# cyberstick3_new.net
KiCad netlist of a schematic drawn in EAGLE
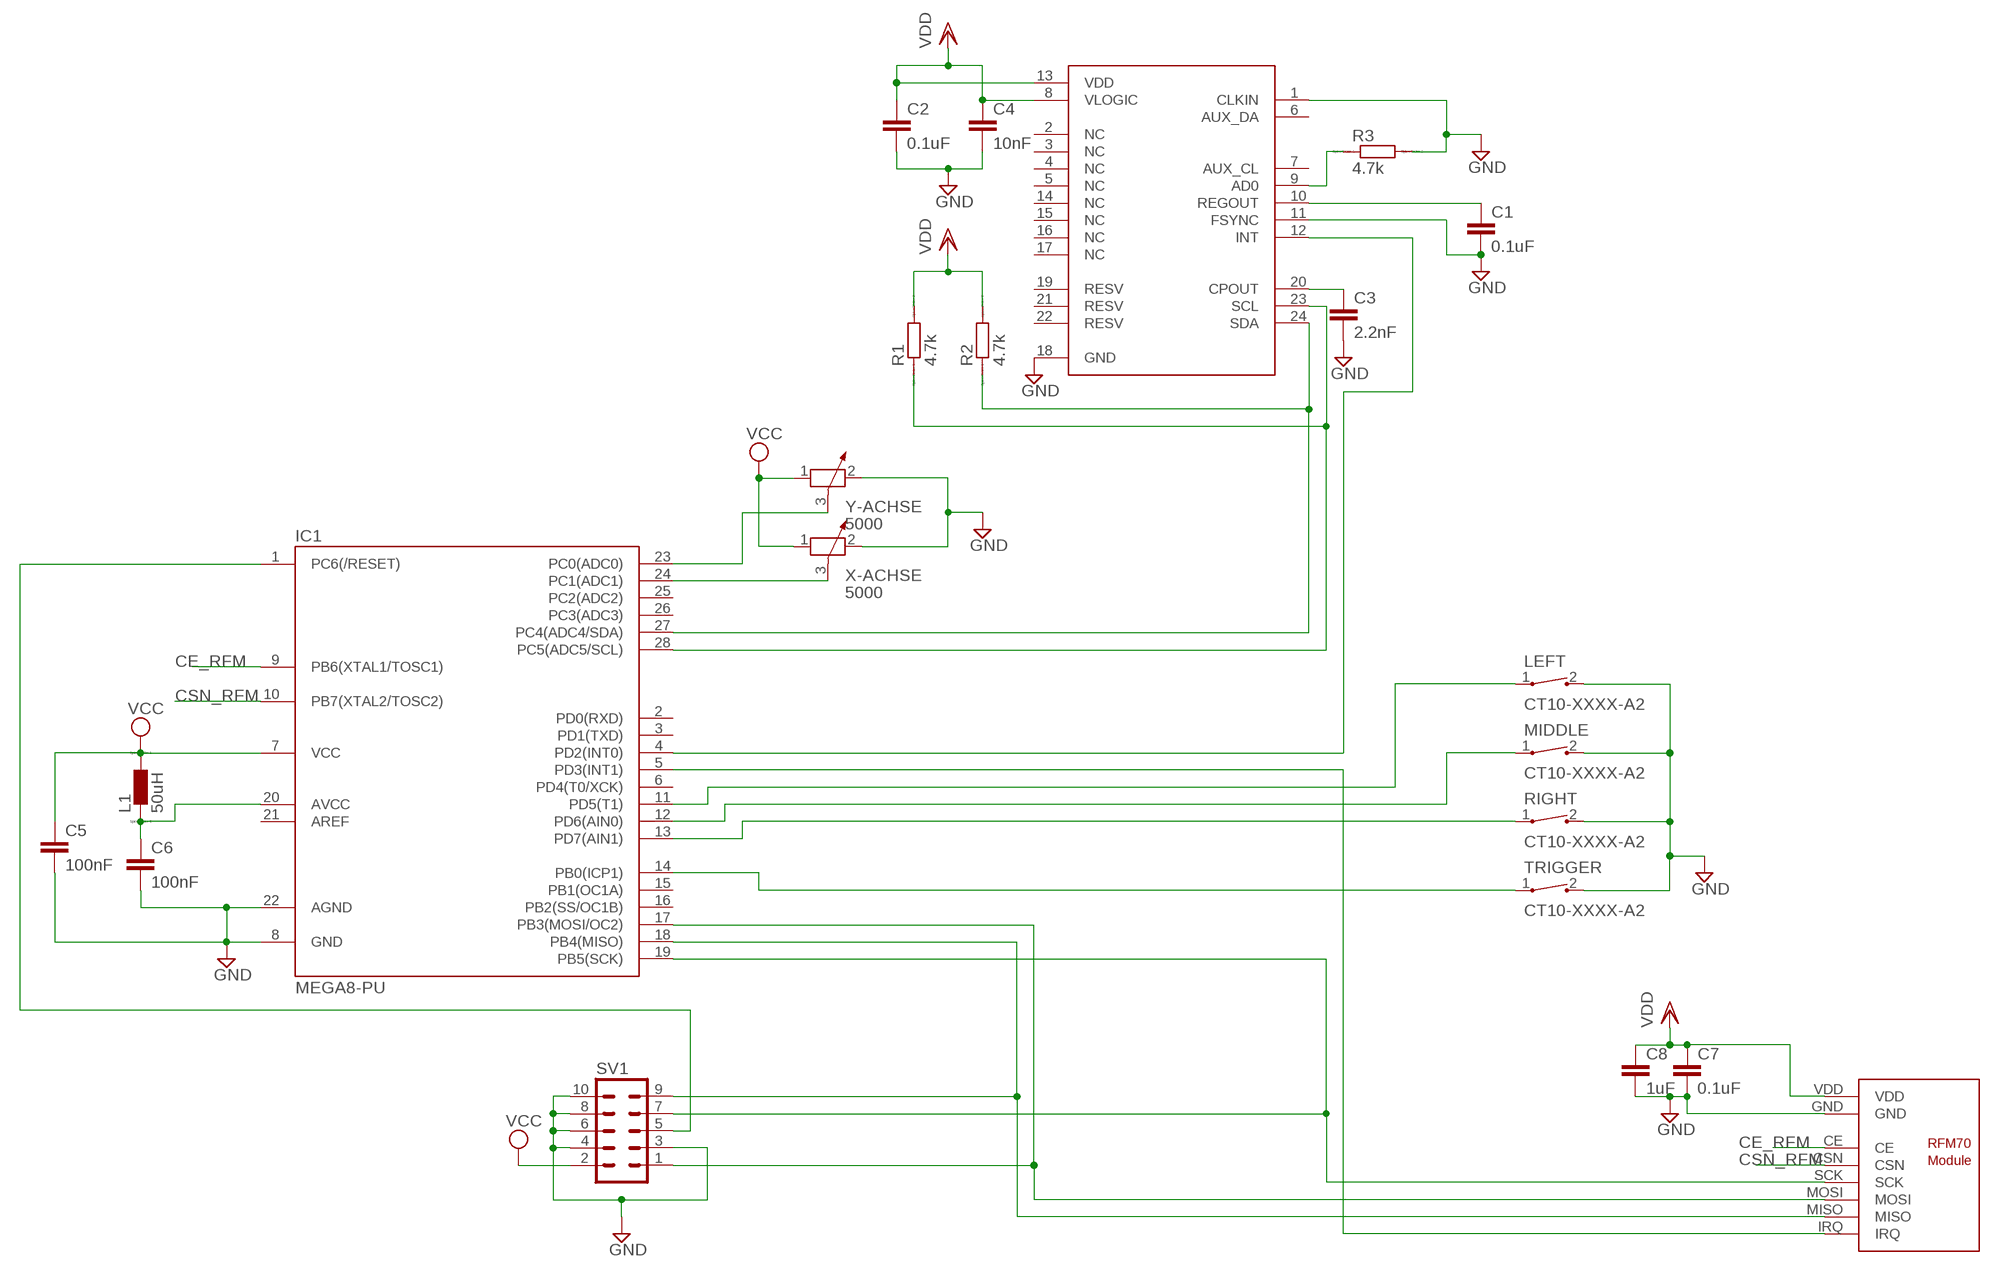
[diagram p0: schematic, sheet 1]

(export (version "E")
  (design (tool "Eeschema 10.0.6"))
  (components
    (comp (ref "C1")
      (value "0.1uF")
      (footprint "eagle-import:C2.5-3")
      (libsource (lib "eagle-import") (part "C2,5-3"))
    )
    (comp (ref "C2")
      (value "0.1uF")
      (footprint "eagle-import:C2.5-3")
      (libsource (lib "eagle-import") (part "C2,5-3"))
    )
    (comp (ref "C3")
      (value "2.2nF")
      (footprint "eagle-import:C2.5-3")
      (libsource (lib "eagle-import") (part "C2,5-3"))
    )
    (comp (ref "C4")
      (value "10nF")
      (footprint "eagle-import:C2.5-3")
      (libsource (lib "eagle-import") (part "C2,5-3"))
    )
    (comp (ref "C5")
      (value "100nF")
      (footprint "eagle-import:C2.5-3")
      (libsource (lib "eagle-import") (part "C2,5-3"))
    )
    (comp (ref "C6")
      (value "100nF")
      (footprint "eagle-import:C2.5-3")
      (libsource (lib "eagle-import") (part "C2,5-3"))
    )
    (comp (ref "C7")
      (value "0.1uF")
      (footprint "eagle-import:C2.5-3")
      (libsource (lib "eagle-import") (part "C2,5-3"))
    )
    (comp (ref "C8")
      (value "1uF")
      (footprint "eagle-import:C2.5-3")
      (libsource (lib "eagle-import") (part "C2,5-3"))
    )
    (comp (ref "IC1")
      (value "MEGA8-PU")
      (footprint "eagle-import:DIL28-3")
      (libsource (lib "eagle-import") (part "MEGA8-PU"))
    )
    (comp (ref "L1")
      (value "50uH")
      (footprint "eagle-import:0204_7")
      (libsource (lib "eagle-import") (part "L0204/7"))
    )
    (comp (ref "LEFT")
      (value "CT10-XXXX-A2")
      (footprint "eagle-import:CT10-XXXX-A2")
      (libsource (lib "eagle-import") (part "CT10-XXXX-A2"))
    )
    (comp (ref "MIDDLE")
      (value "CT10-XXXX-A2")
      (footprint "eagle-import:CT10-XXXX-A2")
      (libsource (lib "eagle-import") (part "CT10-XXXX-A2"))
    )
    (comp (ref "R1")
      (value "4.7k")
      (footprint "eagle-import:0204_7")
      (libsource (lib "eagle-import") (part "R0204/7"))
    )
    (comp (ref "R2")
      (value "4.7k")
      (footprint "eagle-import:0204_7")
      (libsource (lib "eagle-import") (part "R0204/7"))
    )
    (comp (ref "R3")
      (value "4.7k")
      (footprint "eagle-import:0204_7")
      (libsource (lib "eagle-import") (part "R0204/7"))
    )
    (comp (ref "RIGHT")
      (value "CT10-XXXX-A2")
      (footprint "eagle-import:CT10-XXXX-A2")
      (libsource (lib "eagle-import") (part "CT10-XXXX-A2"))
    )
    (comp (ref "SV1")
      (value "MA05-2")
      (footprint "eagle-import:MA05-2")
      (libsource (lib "eagle-import") (part "MA05-2"))
    )
    (comp (ref "TRIGGER")
      (value "CT10-XXXX-A2")
      (footprint "eagle-import:CT10-XXXX-A2")
      (libsource (lib "eagle-import") (part "CT10-XXXX-A2"))
    )
    (comp (ref "U$2")
      (value "RFM70")
      (footprint "eagle-import:RFM70")
      (libsource (lib "eagle-import") (part "RFM70"))
    )
    (comp (ref "U1")
      (value "MPU6050")
      (footprint "eagle-import:MPU6050")
      (libsource (lib "eagle-import") (part "MPU6050"))
    )
    (comp (ref "X-ACHSE")
      (value "5000")
      (footprint "eagle-import:PT-10")
      (libsource (lib "eagle-import") (part "POTENTIOMETER_PT-10"))
    )
    (comp (ref "Y-ACHSE")
      (value "5000")
      (footprint "eagle-import:PT-10")
      (libsource (lib "eagle-import") (part "POTENTIOMETER_PT-10"))
    )
  )
  (nets
    (net (code "1") (name "/CE_RFM") (class "Default")
      (node (ref "IC1") (pin "9") (pinfunction "PB6(XTAL1/TOSC1)_9") (pintype "bidirectional"))
      (node (ref "U$2") (pin "CE") (pinfunction "CE_CE") (pintype "bidirectional"))
    )
    (net (code "2") (name "/CSN_RFM") (class "Default")
      (node (ref "IC1") (pin "10") (pinfunction "PB7(XTAL2/TOSC2)_10") (pintype "bidirectional"))
      (node (ref "U$2") (pin "CSN") (pinfunction "CSN_CSN") (pintype "bidirectional"))
    )
    (net (code "3") (name "GND") (class "Default")
      (node (ref "C1") (pin "2") (pinfunction "2_2") (pintype "passive"))
      (node (ref "C2") (pin "2") (pinfunction "2_2") (pintype "passive"))
      (node (ref "C3") (pin "2") (pinfunction "2_2") (pintype "passive"))
      (node (ref "C4") (pin "2") (pinfunction "2_2") (pintype "passive"))
      (node (ref "C5") (pin "2") (pinfunction "2_2") (pintype "passive"))
      (node (ref "C6") (pin "2") (pinfunction "2_2") (pintype "passive"))
      (node (ref "C7") (pin "2") (pinfunction "2_2") (pintype "passive"))
      (node (ref "C8") (pin "2") (pinfunction "2_2") (pintype "passive"))
      (node (ref "IC1") (pin "22") (pinfunction "AGND_22") (pintype "power_in"))
      (node (ref "IC1") (pin "8") (pinfunction "GND_8") (pintype "power_in"))
      (node (ref "LEFT") (pin "2") (pinfunction "2_2") (pintype "passive"))
      (node (ref "MIDDLE") (pin "2") (pinfunction "2_2") (pintype "passive"))
      (node (ref "R3") (pin "2") (pinfunction "2_2") (pintype "passive"))
      (node (ref "RIGHT") (pin "2") (pinfunction "2_2") (pintype "passive"))
      (node (ref "SV1") (pin "10") (pinfunction "10_10") (pintype "passive"))
      (node (ref "SV1") (pin "3") (pinfunction "3_3") (pintype "passive"))
      (node (ref "SV1") (pin "4") (pinfunction "4_4") (pintype "passive"))
      (node (ref "SV1") (pin "6") (pinfunction "6_6") (pintype "passive"))
      (node (ref "SV1") (pin "8") (pinfunction "8_8") (pintype "passive"))
      (node (ref "TRIGGER") (pin "2") (pinfunction "2_2") (pintype "passive"))
      (node (ref "U$2") (pin "GND") (pinfunction "GND_GND") (pintype "power_in"))
      (node (ref "U1") (pin "1") (pinfunction "CLKIN_1") (pintype "input"))
      (node (ref "U1") (pin "11") (pinfunction "FSYNC_11") (pintype "input"))
      (node (ref "U1") (pin "18") (pinfunction "GND_18") (pintype "power_in"))
      (node (ref "X-ACHSE") (pin "2") (pinfunction "2_2") (pintype "passive"))
      (node (ref "Y-ACHSE") (pin "2") (pinfunction "2_2") (pintype "passive"))
    )
    (net (code "4") (name "Net-(IC1-AVCC)") (class "Default")
      (node (ref "C6") (pin "1") (pinfunction "1_1") (pintype "passive"))
      (node (ref "IC1") (pin "20") (pinfunction "AVCC_20") (pintype "passive"))
      (node (ref "L1") (pin "2") (pinfunction "2_2") (pintype "passive"))
    )
    (net (code "5") (name "Net-(IC1-PB0(ICP1))") (class "Default")
      (node (ref "IC1") (pin "14") (pinfunction "PB0(ICP1)_14") (pintype "bidirectional"))
      (node (ref "TRIGGER") (pin "1") (pinfunction "1_1") (pintype "passive"))
    )
    (net (code "6") (name "Net-(IC1-PB3(MOSI{slash}OC2))") (class "Default")
      (node (ref "IC1") (pin "17") (pinfunction "PB3(MOSI/OC2)_17") (pintype "bidirectional"))
      (node (ref "SV1") (pin "1") (pinfunction "1_1") (pintype "passive"))
      (node (ref "U$2") (pin "MOSI") (pinfunction "MOSI_MOSI") (pintype "bidirectional"))
    )
    (net (code "7") (name "Net-(IC1-PB4(MISO))") (class "Default")
      (node (ref "IC1") (pin "18") (pinfunction "PB4(MISO)_18") (pintype "bidirectional"))
      (node (ref "SV1") (pin "9") (pinfunction "9_9") (pintype "passive"))
      (node (ref "U$2") (pin "MISO") (pinfunction "MISO_MISO") (pintype "bidirectional"))
    )
    (net (code "8") (name "Net-(IC1-PB5(SCK))") (class "Default")
      (node (ref "IC1") (pin "19") (pinfunction "PB5(SCK)_19") (pintype "bidirectional"))
      (node (ref "SV1") (pin "7") (pinfunction "7_7") (pintype "passive"))
      (node (ref "U$2") (pin "SCK") (pinfunction "SCK_SCK") (pintype "bidirectional"))
    )
    (net (code "9") (name "Net-(IC1-PC0(ADC0))") (class "Default")
      (node (ref "IC1") (pin "23") (pinfunction "PC0(ADC0)_23") (pintype "bidirectional"))
      (node (ref "Y-ACHSE") (pin "3") (pinfunction "3_3") (pintype "passive"))
    )
    (net (code "10") (name "Net-(IC1-PC1(ADC1))") (class "Default")
      (node (ref "IC1") (pin "24") (pinfunction "PC1(ADC1)_24") (pintype "bidirectional"))
      (node (ref "X-ACHSE") (pin "3") (pinfunction "3_3") (pintype "passive"))
    )
    (net (code "11") (name "Net-(IC1-PC4(ADC4{slash}SDA))") (class "Default")
      (node (ref "IC1") (pin "27") (pinfunction "PC4(ADC4/SDA)_27") (pintype "bidirectional"))
      (node (ref "R2") (pin "1") (pinfunction "1_1") (pintype "passive"))
      (node (ref "U1") (pin "24") (pinfunction "SDA_24") (pintype "bidirectional"))
    )
    (net (code "12") (name "Net-(IC1-PC5(ADC5{slash}SCL))") (class "Default")
      (node (ref "IC1") (pin "28") (pinfunction "PC5(ADC5/SCL)_28") (pintype "bidirectional"))
      (node (ref "R1") (pin "1") (pinfunction "1_1") (pintype "passive"))
      (node (ref "U1") (pin "23") (pinfunction "SCL_23") (pintype "input"))
    )
    (net (code "13") (name "Net-(IC1-PC6({slash}RESET))") (class "Default")
      (node (ref "IC1") (pin "1") (pinfunction "PC6(/RESET)_1") (pintype "bidirectional"))
      (node (ref "SV1") (pin "5") (pinfunction "5_5") (pintype "passive"))
    )
    (net (code "14") (name "Net-(IC1-PD2(INT0))") (class "Default")
      (node (ref "IC1") (pin "4") (pinfunction "PD2(INT0)_4") (pintype "bidirectional"))
      (node (ref "U1") (pin "12") (pinfunction "INT_12") (pintype "output"))
    )
    (net (code "15") (name "Net-(IC1-PD3(INT1))") (class "Default")
      (node (ref "IC1") (pin "5") (pinfunction "PD3(INT1)_5") (pintype "bidirectional"))
      (node (ref "U$2") (pin "IRQ") (pinfunction "IRQ_IRQ") (pintype "bidirectional"))
    )
    (net (code "16") (name "Net-(IC1-PD5(T1))") (class "Default")
      (node (ref "IC1") (pin "11") (pinfunction "PD5(T1)_11") (pintype "bidirectional"))
      (node (ref "LEFT") (pin "1") (pinfunction "1_1") (pintype "passive"))
    )
    (net (code "17") (name "Net-(IC1-PD6(AIN0))") (class "Default")
      (node (ref "IC1") (pin "12") (pinfunction "PD6(AIN0)_12") (pintype "bidirectional"))
      (node (ref "MIDDLE") (pin "1") (pinfunction "1_1") (pintype "passive"))
    )
    (net (code "18") (name "Net-(IC1-PD7(AIN1))") (class "Default")
      (node (ref "IC1") (pin "13") (pinfunction "PD7(AIN1)_13") (pintype "bidirectional"))
      (node (ref "RIGHT") (pin "1") (pinfunction "1_1") (pintype "passive"))
    )
    (net (code "19") (name "Net-(U1-AD0)") (class "Default")
      (node (ref "R3") (pin "1") (pinfunction "1_1") (pintype "passive"))
      (node (ref "U1") (pin "9") (pinfunction "AD0_9") (pintype "input"))
    )
    (net (code "20") (name "Net-(U1-CPOUT)") (class "Default")
      (node (ref "C3") (pin "1") (pinfunction "1_1") (pintype "passive"))
      (node (ref "U1") (pin "20") (pinfunction "CPOUT_20") (pintype "passive"))
    )
    (net (code "21") (name "Net-(U1-REGOUT)") (class "Default")
      (node (ref "C1") (pin "1") (pinfunction "1_1") (pintype "passive"))
      (node (ref "U1") (pin "10") (pinfunction "REGOUT_10") (pintype "passive"))
    )
    (net (code "22") (name "VCC") (class "Default")
      (node (ref "C5") (pin "1") (pinfunction "1_1") (pintype "passive"))
      (node (ref "IC1") (pin "7") (pinfunction "VCC_7") (pintype "power_in"))
      (node (ref "L1") (pin "1") (pinfunction "1_1") (pintype "passive"))
      (node (ref "SV1") (pin "2") (pinfunction "2_2") (pintype "passive"))
      (node (ref "X-ACHSE") (pin "1") (pinfunction "1_1") (pintype "passive"))
      (node (ref "Y-ACHSE") (pin "1") (pinfunction "1_1") (pintype "passive"))
    )
    (net (code "23") (name "VDD") (class "Default")
      (node (ref "C2") (pin "1") (pinfunction "1_1") (pintype "passive"))
      (node (ref "C4") (pin "1") (pinfunction "1_1") (pintype "passive"))
      (node (ref "C7") (pin "1") (pinfunction "1_1") (pintype "passive"))
      (node (ref "C8") (pin "1") (pinfunction "1_1") (pintype "passive"))
      (node (ref "R1") (pin "2") (pinfunction "2_2") (pintype "passive"))
      (node (ref "R2") (pin "2") (pinfunction "2_2") (pintype "passive"))
      (node (ref "U$2") (pin "VDD") (pinfunction "VDD_VDD") (pintype "power_in"))
      (node (ref "U1") (pin "13") (pinfunction "VDD_13") (pintype "power_in"))
      (node (ref "U1") (pin "8") (pinfunction "VLOGIC_8") (pintype "power_in"))
    )
    (net (code "24") (name "unconnected-(IC1-AREF-Pad21)") (class "Default")
      (node (ref "IC1") (pin "21") (pinfunction "AREF_21") (pintype "passive"))
    )
    (net (code "25") (name "unconnected-(IC1-PB1(OC1A)-Pad15)") (class "Default")
      (node (ref "IC1") (pin "15") (pinfunction "PB1(OC1A)_15") (pintype "bidirectional"))
    )
    (net (code "26") (name "unconnected-(IC1-PB2(SS{slash}OC1B)-Pad16)") (class "Default")
      (node (ref "IC1") (pin "16") (pinfunction "PB2(SS/OC1B)_16") (pintype "bidirectional"))
    )
    (net (code "27") (name "unconnected-(IC1-PC2(ADC2)-Pad25)") (class "Default")
      (node (ref "IC1") (pin "25") (pinfunction "PC2(ADC2)_25") (pintype "bidirectional"))
    )
    (net (code "28") (name "unconnected-(IC1-PC3(ADC3)-Pad26)") (class "Default")
      (node (ref "IC1") (pin "26") (pinfunction "PC3(ADC3)_26") (pintype "bidirectional"))
    )
    (net (code "29") (name "unconnected-(IC1-PD0(RXD)-Pad2)") (class "Default")
      (node (ref "IC1") (pin "2") (pinfunction "PD0(RXD)_2") (pintype "bidirectional"))
    )
    (net (code "30") (name "unconnected-(IC1-PD1(TXD)-Pad3)") (class "Default")
      (node (ref "IC1") (pin "3") (pinfunction "PD1(TXD)_3") (pintype "bidirectional"))
    )
    (net (code "31") (name "unconnected-(IC1-PD4(T0{slash}XCK)-Pad6)") (class "Default")
      (node (ref "IC1") (pin "6") (pinfunction "PD4(T0/XCK)_6") (pintype "bidirectional"))
    )
    (net (code "32") (name "unconnected-(U1-AUX_CL-Pad7)") (class "Default")
      (node (ref "U1") (pin "7") (pinfunction "AUX_CL_7") (pintype "output"))
    )
    (net (code "33") (name "unconnected-(U1-AUX_DA-Pad6)") (class "Default")
      (node (ref "U1") (pin "6") (pinfunction "AUX_DA_6") (pintype "bidirectional"))
    )
    (net (code "34") (name "unconnected-(U1-NC-Pad2)") (class "Default")
      (node (ref "U1") (pin "2") (pinfunction "NC_2") (pintype "no_connect"))
    )
    (net (code "35") (name "unconnected-(U1-NC-Pad3)") (class "Default")
      (node (ref "U1") (pin "3") (pinfunction "NC_3") (pintype "no_connect"))
    )
    (net (code "36") (name "unconnected-(U1-NC-Pad4)") (class "Default")
      (node (ref "U1") (pin "4") (pinfunction "NC_4") (pintype "no_connect"))
    )
    (net (code "37") (name "unconnected-(U1-NC-Pad5)") (class "Default")
      (node (ref "U1") (pin "5") (pinfunction "NC_5") (pintype "no_connect"))
    )
    (net (code "38") (name "unconnected-(U1-NC-Pad14)") (class "Default")
      (node (ref "U1") (pin "14") (pinfunction "NC_14") (pintype "no_connect"))
    )
    (net (code "39") (name "unconnected-(U1-NC-Pad15)") (class "Default")
      (node (ref "U1") (pin "15") (pinfunction "NC_15") (pintype "no_connect"))
    )
    (net (code "40") (name "unconnected-(U1-NC-Pad16)") (class "Default")
      (node (ref "U1") (pin "16") (pinfunction "NC_16") (pintype "no_connect"))
    )
    (net (code "41") (name "unconnected-(U1-NC-Pad17)") (class "Default")
      (node (ref "U1") (pin "17") (pinfunction "NC_17") (pintype "no_connect"))
    )
    (net (code "42") (name "unconnected-(U1-RESV-Pad19)") (class "Default")
      (node (ref "U1") (pin "19") (pinfunction "RESV_19") (pintype "no_connect"))
    )
    (net (code "43") (name "unconnected-(U1-RESV-Pad21)") (class "Default")
      (node (ref "U1") (pin "21") (pinfunction "RESV_21") (pintype "no_connect"))
    )
    (net (code "44") (name "unconnected-(U1-RESV-Pad22)") (class "Default")
      (node (ref "U1") (pin "22") (pinfunction "RESV_22") (pintype "no_connect"))
    )
  )
)
